# 2P_JST-XH_EXT.net
KiCad netlist of a schematic drawn in Altium Designer
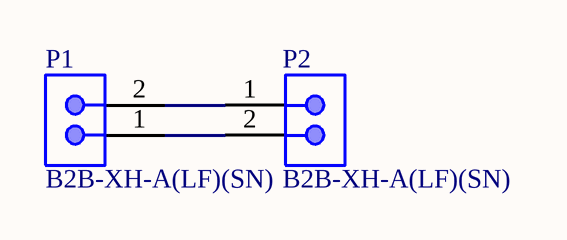
[diagram p0: 2P_JST-XH_EXT.SchDoc]

(export (version "E")
  (design (tool "Eeschema 10.0.6"))
  (components
    (comp (ref "P1")
      (value "B2B-XH-A(LF)(SN)")
      (footprint "JST-B2B-XH-A_V")
      (fields (field (name "MANUFACTURER") "JST"))
      (libsource (lib "Altium Content Vault") (part "CN-1P-M-R2"))
    )
    (comp (ref "P2")
      (value "B2B-XH-A(LF)(SN)")
      (footprint "JST-B2B-XH-A_V")
      (fields (field (name "MANUFACTURER") "JST"))
      (libsource (lib "") (part "CN-1P-M-R2_1"))
    )
  )
  (nets
    (net (code "1") (name "Net-(P1-Pad1)") (class "Default")
      (node (ref "P1") (pin "1") (pinfunction "1_1") (pintype "passive"))
      (node (ref "P2") (pin "2") (pinfunction "2_2") (pintype "passive"))
    )
    (net (code "2") (name "Net-(P1-Pad2)") (class "Default")
      (node (ref "P1") (pin "2") (pinfunction "2_2") (pintype "passive"))
      (node (ref "P2") (pin "1") (pinfunction "1_1") (pintype "passive"))
    )
  )
)
